# CurrentAcquisitionInline.net
KiCad netlist of a schematic drawn in Altium Designer
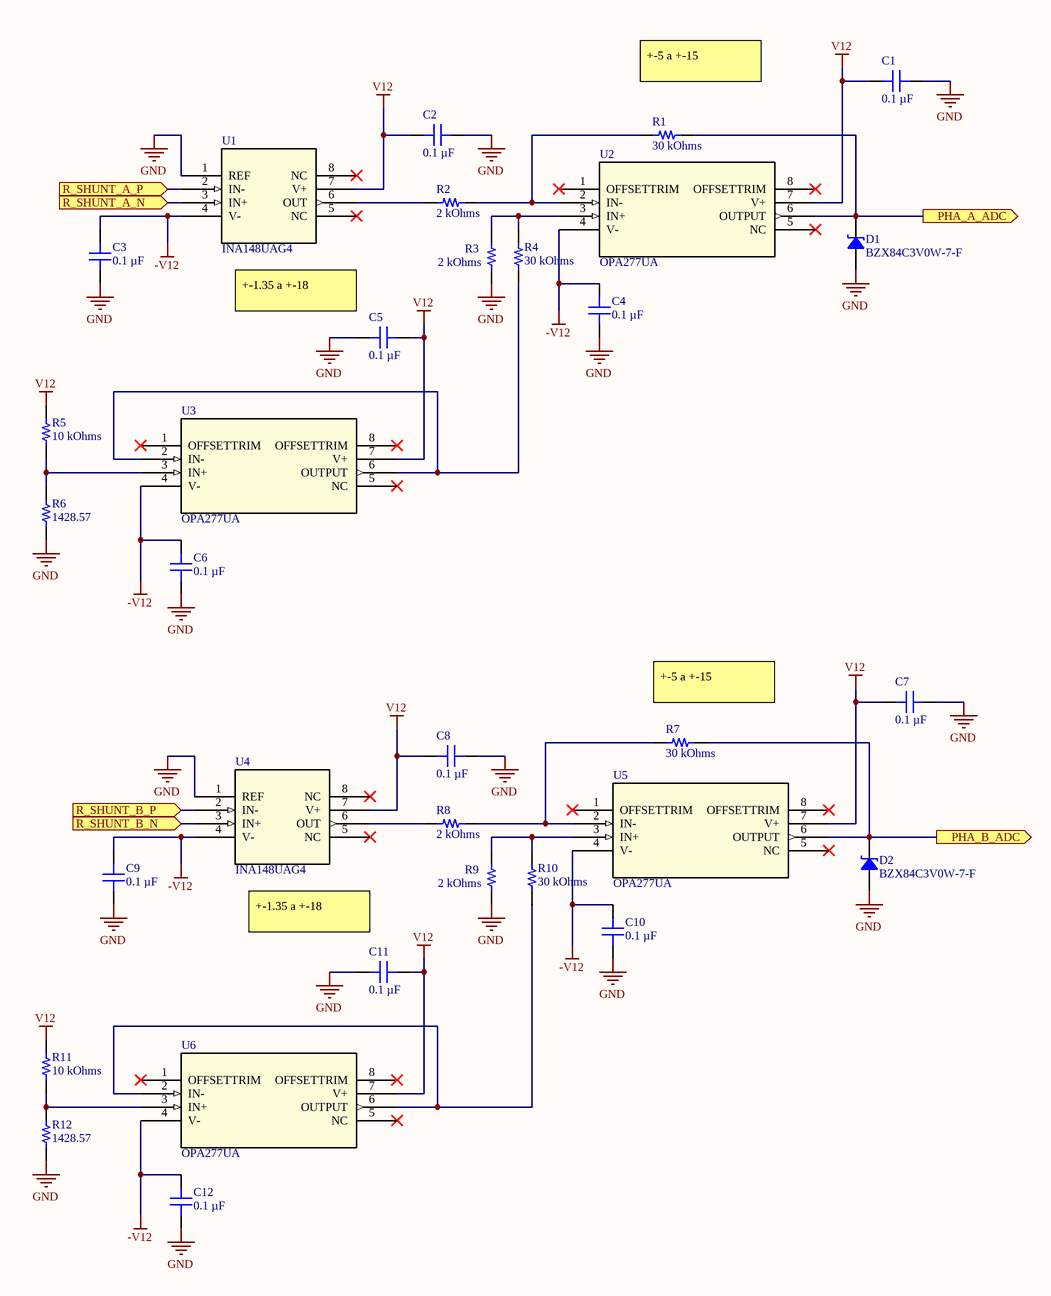
[diagram p0: CurrentAcquisitionInline.SchDoc]

(export (version "E")
  (design (tool "Eeschema 10.0.6"))
  (components
    (comp (ref "C1")
      (value "0.1 µF")
      (footprint "CAP 0805_2012")
      (description "CAP CER 0.1UF 50V X7R 0805")
      (fields (field (name "PART NUMBER") "CC0805MRX7R9BB104") (field (name "MANUFACTURER") "Yageo"))
      (libsource (lib "Celestial Altium Library - altium_library") (part "Capacitor"))
    )
    (comp (ref "C2")
      (value "0.1 µF")
      (footprint "CAP 0805_2012")
      (description "CAP CER 0.1UF 50V X7R 0805")
      (fields (field (name "PART NUMBER") "CC0805MRX7R9BB104") (field (name "MANUFACTURER") "Yageo"))
      (libsource (lib "Celestial Altium Library - altium_library") (part "Capacitor"))
    )
    (comp (ref "C3")
      (value "0.1 µF")
      (footprint "CAP 0805_2012")
      (description "CAP CER 0.1UF 50V X7R 0805")
      (fields (field (name "PART NUMBER") "CC0805MRX7R9BB104") (field (name "MANUFACTURER") "Yageo"))
      (libsource (lib "Celestial Altium Library - altium_library") (part "Capacitor"))
    )
    (comp (ref "C4")
      (value "0.1 µF")
      (footprint "CAP 0805_2012")
      (description "CAP CER 0.1UF 50V X7R 0805")
      (fields (field (name "PART NUMBER") "CC0805MRX7R9BB104") (field (name "MANUFACTURER") "Yageo"))
      (libsource (lib "Celestial Altium Library - altium_library") (part "Capacitor"))
    )
    (comp (ref "C5")
      (value "0.1 µF")
      (footprint "CAP 0805_2012")
      (description "CAP CER 0.1UF 50V X7R 0805")
      (fields (field (name "PART NUMBER") "CC0805MRX7R9BB104") (field (name "MANUFACTURER") "Yageo"))
      (libsource (lib "Celestial Altium Library - altium_library") (part "Capacitor"))
    )
    (comp (ref "C6")
      (value "0.1 µF")
      (footprint "CAP 0805_2012")
      (description "CAP CER 0.1UF 50V X7R 0805")
      (fields (field (name "PART NUMBER") "CC0805MRX7R9BB104") (field (name "MANUFACTURER") "Yageo"))
      (libsource (lib "Celestial Altium Library - altium_library") (part "Capacitor"))
    )
    (comp (ref "C7")
      (value "0.1 µF")
      (footprint "CAP 0805_2012")
      (description "CAP CER 0.1UF 50V X7R 0805")
      (fields (field (name "PART NUMBER") "CC0805MRX7R9BB104") (field (name "MANUFACTURER") "Yageo"))
      (libsource (lib "Celestial Altium Library - altium_library") (part "Capacitor"))
    )
    (comp (ref "C8")
      (value "0.1 µF")
      (footprint "CAP 0805_2012")
      (description "CAP CER 0.1UF 50V X7R 0805")
      (fields (field (name "PART NUMBER") "CC0805MRX7R9BB104") (field (name "MANUFACTURER") "Yageo"))
      (libsource (lib "Celestial Altium Library - altium_library") (part "Capacitor"))
    )
    (comp (ref "C9")
      (value "0.1 µF")
      (footprint "CAP 0805_2012")
      (description "CAP CER 0.1UF 50V X7R 0805")
      (fields (field (name "PART NUMBER") "CC0805MRX7R9BB104") (field (name "MANUFACTURER") "Yageo"))
      (libsource (lib "Celestial Altium Library - altium_library") (part "Capacitor"))
    )
    (comp (ref "C10")
      (value "0.1 µF")
      (footprint "CAP 0805_2012")
      (description "CAP CER 0.1UF 50V X7R 0805")
      (fields (field (name "PART NUMBER") "CC0805MRX7R9BB104") (field (name "MANUFACTURER") "Yageo"))
      (libsource (lib "Celestial Altium Library - altium_library") (part "Capacitor"))
    )
    (comp (ref "C11")
      (value "0.1 µF")
      (footprint "CAP 0805_2012")
      (description "CAP CER 0.1UF 50V X7R 0805")
      (fields (field (name "PART NUMBER") "CC0805MRX7R9BB104") (field (name "MANUFACTURER") "Yageo"))
      (libsource (lib "Celestial Altium Library - altium_library") (part "Capacitor"))
    )
    (comp (ref "C12")
      (value "0.1 µF")
      (footprint "CAP 0805_2012")
      (description "CAP CER 0.1UF 50V X7R 0805")
      (fields (field (name "PART NUMBER") "CC0805MRX7R9BB104") (field (name "MANUFACTURER") "Yageo"))
      (libsource (lib "Celestial Altium Library - altium_library") (part "Capacitor"))
    )
    (comp (ref "D1")
      (value "BZX84C3V0W-7-F")
      (footprint "DIODES SOT-323-3")
      (description "DIODE ZENER 3V 200MW SOT323")
      (fields (field (name "MANUFACTURER") "Diodes Incorporated") (field (name "TOLERANCE") "±7%"))
      (libsource (lib "Celestial Altium Library - altium_library") (part "Diode Zener"))
    )
    (comp (ref "D2")
      (value "BZX84C3V0W-7-F")
      (footprint "DIODES SOT-323-3")
      (description "DIODE ZENER 3V 200MW SOT323")
      (fields (field (name "MANUFACTURER") "Diodes Incorporated") (field (name "TOLERANCE") "±7%"))
      (libsource (lib "Celestial Altium Library - altium_library") (part "Diode Zener"))
    )
    (comp (ref "R1")
      (value "30 kOhms")
      (footprint "RES 0805_2012")
      (description "RES SMD 200K OHM 5% 1/8W 0805")
      (fields (field (name "PART NUMBER") "CR0805-JW-204ELF") (field (name "MANUFACTURER") "Bourns Inc."))
      (libsource (lib "Celestial Altium Library - altium_library") (part "Resistor"))
    )
    (comp (ref "R2")
      (value "2 kOhms")
      (footprint "RES 0805_2012")
      (description "RES SMD 200K OHM 5% 1/8W 0805")
      (fields (field (name "PART NUMBER") "CR0805-JW-204ELF") (field (name "MANUFACTURER") "Bourns Inc."))
      (libsource (lib "Celestial Altium Library - altium_library") (part "Resistor"))
    )
    (comp (ref "R3")
      (value "2 kOhms")
      (footprint "RES 0805_2012")
      (description "RES SMD 200K OHM 5% 1/8W 0805")
      (fields (field (name "PART NUMBER") "CR0805-JW-204ELF") (field (name "MANUFACTURER") "Bourns Inc."))
      (libsource (lib "Celestial Altium Library - altium_library") (part "Resistor"))
    )
    (comp (ref "R4")
      (value "30 kOhms")
      (footprint "RES 0805_2012")
      (description "RES SMD 200K OHM 5% 1/8W 0805")
      (fields (field (name "PART NUMBER") "CR0805-JW-204ELF") (field (name "MANUFACTURER") "Bourns Inc."))
      (libsource (lib "Celestial Altium Library - altium_library") (part "Resistor"))
    )
    (comp (ref "R5")
      (value "10 kOhms")
      (footprint "RES 0805_2012")
      (description "RES SMD 200K OHM 5% 1/8W 0805")
      (fields (field (name "PART NUMBER") "CR0805-JW-204ELF") (field (name "MANUFACTURER") "Bourns Inc."))
      (libsource (lib "") (part "Resistor_1"))
    )
    (comp (ref "R6")
      (value "1428.57")
      (footprint "RES 0805_2012")
      (description "RES SMD 200K OHM 5% 1/8W 0805")
      (fields (field (name "PART NUMBER") "CR0805-JW-204ELF") (field (name "MANUFACTURER") "Bourns Inc."))
      (libsource (lib "Celestial Altium Library - altium_library") (part "Resistor"))
    )
    (comp (ref "R7")
      (value "30 kOhms")
      (footprint "RES 0805_2012")
      (description "RES SMD 200K OHM 5% 1/8W 0805")
      (fields (field (name "PART NUMBER") "CR0805-JW-204ELF") (field (name "MANUFACTURER") "Bourns Inc."))
      (libsource (lib "") (part "Resistor_1"))
    )
    (comp (ref "R8")
      (value "2 kOhms")
      (footprint "RES 0805_2012")
      (description "RES SMD 200K OHM 5% 1/8W 0805")
      (fields (field (name "PART NUMBER") "CR0805-JW-204ELF") (field (name "MANUFACTURER") "Bourns Inc."))
      (libsource (lib "Celestial Altium Library - altium_library") (part "Resistor"))
    )
    (comp (ref "R9")
      (value "2 kOhms")
      (footprint "RES 0805_2012")
      (description "RES SMD 200K OHM 5% 1/8W 0805")
      (fields (field (name "PART NUMBER") "CR0805-JW-204ELF") (field (name "MANUFACTURER") "Bourns Inc."))
      (libsource (lib "Celestial Altium Library - altium_library") (part "Resistor"))
    )
    (comp (ref "R10")
      (value "30 kOhms")
      (footprint "RES 0805_2012")
      (description "RES SMD 200K OHM 5% 1/8W 0805")
      (fields (field (name "PART NUMBER") "CR0805-JW-204ELF") (field (name "MANUFACTURER") "Bourns Inc."))
      (libsource (lib "Celestial Altium Library - altium_library") (part "Resistor"))
    )
    (comp (ref "R11")
      (value "10 kOhms")
      (footprint "RES 0805_2012")
      (description "RES SMD 200K OHM 5% 1/8W 0805")
      (fields (field (name "PART NUMBER") "CR0805-JW-204ELF") (field (name "MANUFACTURER") "Bourns Inc."))
      (libsource (lib "") (part "Resistor_1"))
    )
    (comp (ref "R12")
      (value "1428.57")
      (footprint "RES 0805_2012")
      (description "RES SMD 200K OHM 5% 1/8W 0805")
      (fields (field (name "PART NUMBER") "CR0805-JW-204ELF") (field (name "MANUFACTURER") "Bourns Inc."))
      (libsource (lib "Celestial Altium Library - altium_library") (part "Resistor"))
    )
    (comp (ref "U1")
      (value "INA148UAG4")
      (footprint "D8")
      (description "No Description Available")
      (fields (field (name "COPYRIGHT") "Copyright (C) 2023 Ultra Librarian. All rights reserved."))
      (libsource (lib "INA148UAG4") (part "INA148UAG4"))
    )
    (comp (ref "U2")
      (value "OPA277UA")
      (footprint "D8")
      (description "No Description Available")
      (fields (field (name "COPYRIGHT") "Copyright (C) 2023 Ultra Librarian. All rights reserved."))
      (libsource (lib "OPA277UA") (part "OPA277UA"))
    )
    (comp (ref "U3")
      (value "OPA277UA")
      (footprint "D8")
      (description "No Description Available")
      (fields (field (name "COPYRIGHT") "Copyright (C) 2023 Ultra Librarian. All rights reserved."))
      (libsource (lib "OPA277UA") (part "OPA277UA"))
    )
    (comp (ref "U4")
      (value "INA148UAG4")
      (footprint "D8")
      (description "No Description Available")
      (fields (field (name "COPYRIGHT") "Copyright (C) 2023 Ultra Librarian. All rights reserved."))
      (libsource (lib "INA148UAG4") (part "INA148UAG4"))
    )
    (comp (ref "U5")
      (value "OPA277UA")
      (footprint "D8")
      (description "No Description Available")
      (fields (field (name "COPYRIGHT") "Copyright (C) 2023 Ultra Librarian. All rights reserved."))
      (libsource (lib "OPA277UA") (part "OPA277UA"))
    )
    (comp (ref "U6")
      (value "OPA277UA")
      (footprint "D8")
      (description "No Description Available")
      (fields (field (name "COPYRIGHT") "Copyright (C) 2023 Ultra Librarian. All rights reserved."))
      (libsource (lib "OPA277UA") (part "OPA277UA"))
    )
  )
  (nets
    (net (code "1") (name "-V12") (class "Default")
      (node (ref "C10") (pin "2") (pinfunction "2_2") (pintype "passive"))
      (node (ref "C12") (pin "2") (pinfunction "2_2") (pintype "passive"))
      (node (ref "C3") (pin "2") (pinfunction "2_2") (pintype "passive"))
      (node (ref "C4") (pin "2") (pinfunction "2_2") (pintype "passive"))
      (node (ref "C6") (pin "2") (pinfunction "2_2") (pintype "passive"))
      (node (ref "C9") (pin "2") (pinfunction "2_2") (pintype "passive"))
      (node (ref "U1") (pin "4") (pinfunction "V-_4") (pintype "power_in"))
      (node (ref "U2") (pin "4") (pinfunction "V-_4") (pintype "power_in"))
      (node (ref "U3") (pin "4") (pinfunction "V-_4") (pintype "power_in"))
      (node (ref "U4") (pin "4") (pinfunction "V-_4") (pintype "power_in"))
      (node (ref "U5") (pin "4") (pinfunction "V-_4") (pintype "power_in"))
      (node (ref "U6") (pin "4") (pinfunction "V-_4") (pintype "power_in"))
    )
    (net (code "2") (name "/PHA_A_ADC") (class "Default")
      (node (ref "D1") (pin "2") (pinfunction "2_2") (pintype "passive"))
      (node (ref "R1") (pin "1") (pinfunction "1_1") (pintype "passive"))
      (node (ref "U2") (pin "6") (pinfunction "OUTPUT_6") (pintype "output"))
    )
    (net (code "3") (name "/PHA_B_ADC") (class "Default")
      (node (ref "D2") (pin "2") (pinfunction "2_2") (pintype "passive"))
      (node (ref "R7") (pin "1") (pinfunction "1_1") (pintype "passive"))
      (node (ref "U5") (pin "6") (pinfunction "OUTPUT_6") (pintype "output"))
    )
    (net (code "4") (name "/R_SHUNT_A_N") (class "Default")
      (node (ref "U1") (pin "3") (pinfunction "IN+_3") (pintype "input"))
    )
    (net (code "5") (name "/R_SHUNT_A_P") (class "Default")
      (node (ref "U1") (pin "2") (pinfunction "IN-_2") (pintype "input"))
    )
    (net (code "6") (name "/R_SHUNT_B_N") (class "Default")
      (node (ref "U4") (pin "3") (pinfunction "IN+_3") (pintype "input"))
    )
    (net (code "7") (name "/R_SHUNT_B_P") (class "Default")
      (node (ref "U4") (pin "2") (pinfunction "IN-_2") (pintype "input"))
    )
    (net (code "8") (name "GND") (class "Default")
      (node (ref "C1") (pin "2") (pinfunction "2_2") (pintype "passive"))
      (node (ref "C10") (pin "1") (pinfunction "1_1") (pintype "passive"))
      (node (ref "C11") (pin "2") (pinfunction "2_2") (pintype "passive"))
      (node (ref "C12") (pin "1") (pinfunction "1_1") (pintype "passive"))
      (node (ref "C2") (pin "2") (pinfunction "2_2") (pintype "passive"))
      (node (ref "C3") (pin "1") (pinfunction "1_1") (pintype "passive"))
      (node (ref "C4") (pin "1") (pinfunction "1_1") (pintype "passive"))
      (node (ref "C5") (pin "2") (pinfunction "2_2") (pintype "passive"))
      (node (ref "C6") (pin "1") (pinfunction "1_1") (pintype "passive"))
      (node (ref "C7") (pin "2") (pinfunction "2_2") (pintype "passive"))
      (node (ref "C8") (pin "2") (pinfunction "2_2") (pintype "passive"))
      (node (ref "C9") (pin "1") (pinfunction "1_1") (pintype "passive"))
      (node (ref "D1") (pin "1") (pinfunction "1_1") (pintype "passive"))
      (node (ref "D2") (pin "1") (pinfunction "1_1") (pintype "passive"))
      (node (ref "R12") (pin "2") (pinfunction "2_2") (pintype "passive"))
      (node (ref "R3") (pin "1") (pinfunction "1_1") (pintype "passive"))
      (node (ref "R6") (pin "2") (pinfunction "2_2") (pintype "passive"))
      (node (ref "R9") (pin "2") (pinfunction "2_2") (pintype "passive"))
      (node (ref "U1") (pin "1") (pinfunction "REF_1") (pintype "passive"))
      (node (ref "U4") (pin "1") (pinfunction "REF_1") (pintype "passive"))
    )
    (net (code "9") (name "Net-(U1-OUT)") (class "Default")
      (node (ref "R2") (pin "2") (pinfunction "2_2") (pintype "passive"))
      (node (ref "U1") (pin "6") (pinfunction "OUT_6") (pintype "output"))
    )
    (net (code "10") (name "Net-(U2-IN+)") (class "Default")
      (node (ref "R3") (pin "2") (pinfunction "2_2") (pintype "passive"))
      (node (ref "R4") (pin "1") (pinfunction "1_1") (pintype "passive"))
      (node (ref "U2") (pin "3") (pinfunction "IN+_3") (pintype "input"))
    )
    (net (code "11") (name "Net-(U2-IN-)") (class "Default")
      (node (ref "R1") (pin "2") (pinfunction "2_2") (pintype "passive"))
      (node (ref "R2") (pin "1") (pinfunction "1_1") (pintype "passive"))
      (node (ref "U2") (pin "2") (pinfunction "IN-_2") (pintype "input"))
    )
    (net (code "12") (name "Net-(U3-IN+)") (class "Default")
      (node (ref "R5") (pin "1") (pinfunction "1_1") (pintype "passive"))
      (node (ref "R6") (pin "1") (pinfunction "1_1") (pintype "passive"))
      (node (ref "U3") (pin "3") (pinfunction "IN+_3") (pintype "input"))
    )
    (net (code "13") (name "Net-(U3-IN-)") (class "Default")
      (node (ref "R4") (pin "2") (pinfunction "2_2") (pintype "passive"))
      (node (ref "U3") (pin "2") (pinfunction "IN-_2") (pintype "input"))
      (node (ref "U3") (pin "6") (pinfunction "OUTPUT_6") (pintype "output"))
    )
    (net (code "14") (name "Net-(U4-OUT)") (class "Default")
      (node (ref "R8") (pin "1") (pinfunction "1_1") (pintype "passive"))
      (node (ref "U4") (pin "6") (pinfunction "OUT_6") (pintype "output"))
    )
    (net (code "15") (name "Net-(U5-IN+)") (class "Default")
      (node (ref "R10") (pin "1") (pinfunction "1_1") (pintype "passive"))
      (node (ref "R9") (pin "1") (pinfunction "1_1") (pintype "passive"))
      (node (ref "U5") (pin "3") (pinfunction "IN+_3") (pintype "input"))
    )
    (net (code "16") (name "Net-(U5-IN-)") (class "Default")
      (node (ref "R7") (pin "1") (pinfunction "1_1") (pintype "passive"))
      (node (ref "R8") (pin "2") (pinfunction "2_2") (pintype "passive"))
      (node (ref "U5") (pin "2") (pinfunction "IN-_2") (pintype "input"))
    )
    (net (code "17") (name "Net-(U6-IN+)") (class "Default")
      (node (ref "R11") (pin "1") (pinfunction "1_1") (pintype "passive"))
      (node (ref "R12") (pin "1") (pinfunction "1_1") (pintype "passive"))
      (node (ref "U6") (pin "3") (pinfunction "IN+_3") (pintype "input"))
    )
    (net (code "18") (name "Net-(U6-IN-)") (class "Default")
      (node (ref "R10") (pin "2") (pinfunction "2_2") (pintype "passive"))
      (node (ref "U6") (pin "2") (pinfunction "IN-_2") (pintype "input"))
      (node (ref "U6") (pin "6") (pinfunction "OUTPUT_6") (pintype "output"))
    )
    (net (code "19") (name "V12") (class "Default")
      (node (ref "C1") (pin "1") (pinfunction "1_1") (pintype "passive"))
      (node (ref "C11") (pin "1") (pinfunction "1_1") (pintype "passive"))
      (node (ref "C2") (pin "1") (pinfunction "1_1") (pintype "passive"))
      (node (ref "C5") (pin "1") (pinfunction "1_1") (pintype "passive"))
      (node (ref "C7") (pin "1") (pinfunction "1_1") (pintype "passive"))
      (node (ref "C8") (pin "1") (pinfunction "1_1") (pintype "passive"))
      (node (ref "R11") (pin "1") (pinfunction "1_1") (pintype "passive"))
      (node (ref "R5") (pin "1") (pinfunction "1_1") (pintype "passive"))
      (node (ref "U1") (pin "7") (pinfunction "V+_7") (pintype "power_in"))
      (node (ref "U2") (pin "7") (pinfunction "V+_7") (pintype "power_in"))
      (node (ref "U3") (pin "7") (pinfunction "V+_7") (pintype "power_in"))
      (node (ref "U4") (pin "7") (pinfunction "V+_7") (pintype "power_in"))
      (node (ref "U5") (pin "7") (pinfunction "V+_7") (pintype "power_in"))
      (node (ref "U6") (pin "7") (pinfunction "V+_7") (pintype "power_in"))
    )
    (net (code "20") (name "unconnected-(U1-NC-Pad5)") (class "Default")
      (node (ref "U1") (pin "5") (pinfunction "NC_5") (pintype "passive+no_connect"))
    )
    (net (code "21") (name "unconnected-(U1-NC-Pad8)") (class "Default")
      (node (ref "U1") (pin "8") (pinfunction "NC_8") (pintype "passive+no_connect"))
    )
    (net (code "22") (name "unconnected-(U2-NC-Pad5)") (class "Default")
      (node (ref "U2") (pin "5") (pinfunction "NC_5") (pintype "passive+no_connect"))
    )
    (net (code "23") (name "unconnected-(U2-OFFSETTRIM-Pad1)") (class "Default")
      (node (ref "U2") (pin "1") (pinfunction "OFFSETTRIM_1") (pintype "passive+no_connect"))
    )
    (net (code "24") (name "unconnected-(U2-OFFSETTRIM-Pad8)") (class "Default")
      (node (ref "U2") (pin "8") (pinfunction "OFFSETTRIM_8") (pintype "passive+no_connect"))
    )
    (net (code "25") (name "unconnected-(U3-NC-Pad5)") (class "Default")
      (node (ref "U3") (pin "5") (pinfunction "NC_5") (pintype "passive+no_connect"))
    )
    (net (code "26") (name "unconnected-(U3-OFFSETTRIM-Pad1)") (class "Default")
      (node (ref "U3") (pin "1") (pinfunction "OFFSETTRIM_1") (pintype "passive+no_connect"))
    )
    (net (code "27") (name "unconnected-(U3-OFFSETTRIM-Pad8)") (class "Default")
      (node (ref "U3") (pin "8") (pinfunction "OFFSETTRIM_8") (pintype "passive+no_connect"))
    )
    (net (code "28") (name "unconnected-(U4-NC-Pad5)") (class "Default")
      (node (ref "U4") (pin "5") (pinfunction "NC_5") (pintype "passive+no_connect"))
    )
    (net (code "29") (name "unconnected-(U4-NC-Pad8)") (class "Default")
      (node (ref "U4") (pin "8") (pinfunction "NC_8") (pintype "passive+no_connect"))
    )
    (net (code "30") (name "unconnected-(U5-NC-Pad5)") (class "Default")
      (node (ref "U5") (pin "5") (pinfunction "NC_5") (pintype "passive+no_connect"))
    )
    (net (code "31") (name "unconnected-(U5-OFFSETTRIM-Pad1)") (class "Default")
      (node (ref "U5") (pin "1") (pinfunction "OFFSETTRIM_1") (pintype "passive+no_connect"))
    )
    (net (code "32") (name "unconnected-(U5-OFFSETTRIM-Pad8)") (class "Default")
      (node (ref "U5") (pin "8") (pinfunction "OFFSETTRIM_8") (pintype "passive+no_connect"))
    )
    (net (code "33") (name "unconnected-(U6-NC-Pad5)") (class "Default")
      (node (ref "U6") (pin "5") (pinfunction "NC_5") (pintype "passive+no_connect"))
    )
    (net (code "34") (name "unconnected-(U6-OFFSETTRIM-Pad1)") (class "Default")
      (node (ref "U6") (pin "1") (pinfunction "OFFSETTRIM_1") (pintype "passive+no_connect"))
    )
    (net (code "35") (name "unconnected-(U6-OFFSETTRIM-Pad8)") (class "Default")
      (node (ref "U6") (pin "8") (pinfunction "OFFSETTRIM_8") (pintype "passive+no_connect"))
    )
  )
)
